# PWMsch.net
KiCad netlist of a schematic drawn in Altium Designer
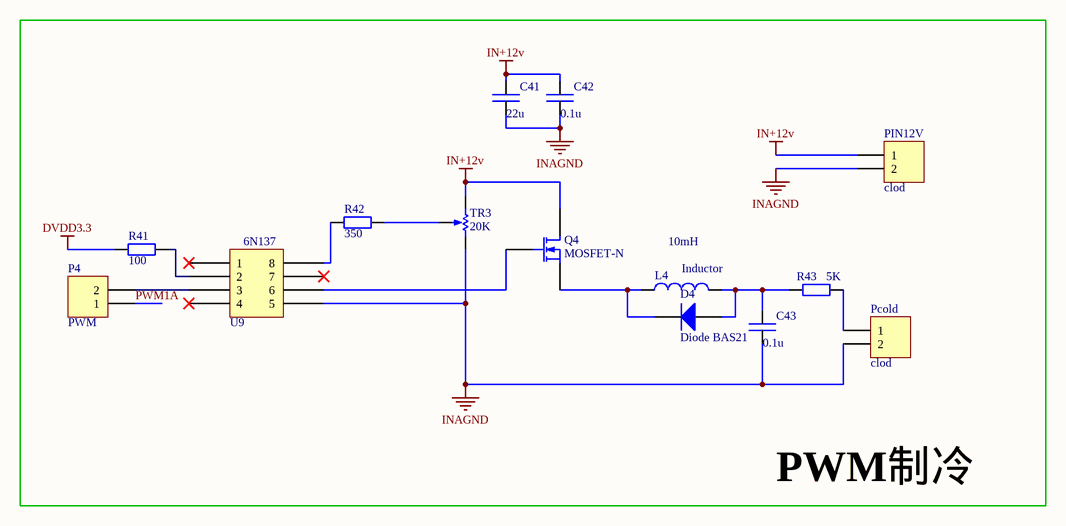
[diagram p0: PWMsch.SchDoc]

(export (version "E")
  (design (tool "Eeschema 10.0.6"))
  (components
    (comp (ref "C41") (value "22u") (footprint "4*4.5 贴片电解电容") (libsource (lib "LST") (part "Cap")))
    (comp (ref "C42") (value "0.1u") (footprint "0805") (libsource (lib "LST") (part "Cap")))
    (comp (ref "C43") (value "0.1u") (footprint "0805") (libsource (lib "LST") (part "Cap")))
    (comp (ref "D4")
      (value "Diode BAS21")
      (footprint "DIODE-SMA")
      (description "Silicon Switching Diode for High-Speed, High-Voltage Switching")
      (fields (field (name "PUBLISHER") "Altium Limited"))
      (libsource (lib "Miscellaneous Devices") (part "Diode BAS21"))
    )
    (comp (ref "L4")
      (value "Inductor")
      (footprint "1206")
      (fields (field (name "ALTIUM_VALUE") "10mH") (field (name "PUBLISHER") "Altium Limited"))
      (libsource (lib "Miscellaneous Devices") (part "Inductor"))
    )
    (comp (ref "P4")
      (value "PWM")
      (footprint "HDR1X2")
      (description "Header, 2-Pin")
      (fields (field (name "PUBLISHER") "Altium Limited"))
      (libsource (lib "") (part "Header 2_1"))
    )
    (comp (ref "Pcold")
      (value "clod")
      (footprint "HDR1X2")
      (description "Header, 2-Pin")
      (fields (field (name "PUBLISHER") "Altium Limited"))
      (libsource (lib "Miscellaneous Connectors") (part "Header 2"))
    )
    (comp (ref "PIN12V")
      (value "clod")
      (footprint "HDR1X2")
      (description "Header, 2-Pin")
      (fields (field (name "PUBLISHER") "Altium Limited"))
      (libsource (lib "Miscellaneous Connectors") (part "Header 2"))
    )
    (comp (ref "Q4")
      (value "MOSFET-N")
      (footprint "TIP122-带卧式散热")
      (description "N-Channel MOSFET")
      (fields (field (name "PUBLISHER") "Altium Limited"))
      (libsource (lib "Miscellaneous Devices") (part "MOSFET-N"))
    )
    (comp (ref "R41")
      (value "100")
      (footprint "0805")
      (description "Resistor")
      (fields (field (name "Comment") "Res2") (field (name "PUBLISHER") "Altium Limited"))
      (libsource (lib "Miscellaneous Devices") (part "Res2"))
    )
    (comp (ref "R42")
      (value "350")
      (footprint "0805")
      (description "Resistor")
      (fields (field (name "Comment") "Res2") (field (name "PUBLISHER") "Altium Limited"))
      (libsource (lib "Miscellaneous Devices") (part "Res2"))
    )
    (comp (ref "R43")
      (value "5K")
      (footprint "1206")
      (description "Resistor")
      (fields (field (name "Comment") "Res2") (field (name "PUBLISHER") "Altium Limited"))
      (libsource (lib "") (part "Res2_1"))
    )
    (comp (ref "TR3")
      (value "20K")
      (footprint "VR5")
      (description "Potentiometer")
      (fields (field (name "Comment") "RPot") (field (name "PUBLISHER") "Altium Limited"))
      (libsource (lib "Miscellaneous Devices") (part "RPot"))
    )
    (comp (ref "U9") (value "6N137") (footprint "SOIC8") (libsource (lib "cold") (part "6N137")))
  )
  (nets
    (net (code "1") (name "/PWM1A") (class "Default")
      (node (ref "P4") (pin "1") (pinfunction "1_1") (pintype "passive"))
    )
    (net (code "2") (name "DVDD3.3") (class "Default")
      (node (ref "R41") (pin "2") (pinfunction "2_2") (pintype "passive"))
    )
    (net (code "3") (name "IN+12v") (class "Default")
      (node (ref "C41") (pin "1") (pinfunction "1_1") (pintype "passive"))
      (node (ref "C42") (pin "1") (pinfunction "1_1") (pintype "passive"))
      (node (ref "PIN12V") (pin "1") (pinfunction "1_1") (pintype "passive"))
      (node (ref "Q4") (pin "2") (pinfunction "D_2") (pintype "passive"))
      (node (ref "TR3") (pin "1") (pinfunction "TOP_1") (pintype "passive"))
    )
    (net (code "4") (name "INAGND") (class "Default")
      (node (ref "C41") (pin "2") (pinfunction "2_2") (pintype "passive"))
      (node (ref "C42") (pin "2") (pinfunction "2_2") (pintype "passive"))
      (node (ref "C43") (pin "2") (pinfunction "2_2") (pintype "passive"))
      (node (ref "PIN12V") (pin "2") (pinfunction "2_2") (pintype "passive"))
      (node (ref "Pcold") (pin "2") (pinfunction "2_2") (pintype "passive"))
      (node (ref "TR3") (pin "3") (pinfunction "BOT_3") (pintype "passive"))
      (node (ref "U9") (pin "5") (pinfunction "5_5") (pintype "passive"))
    )
    (net (code "5") (name "Net-(D4-A)") (class "Default")
      (node (ref "C43") (pin "1") (pinfunction "1_1") (pintype "passive"))
      (node (ref "D4") (pin "1") (pinfunction "A_1") (pintype "passive"))
      (node (ref "L4") (pin "2") (pinfunction "2_2") (pintype "passive"))
      (node (ref "R43") (pin "1") (pinfunction "1_1") (pintype "passive"))
    )
    (net (code "6") (name "Net-(D4-K)") (class "Default")
      (node (ref "D4") (pin "3") (pinfunction "K_3") (pintype "passive"))
      (node (ref "L4") (pin "1") (pinfunction "1_1") (pintype "passive"))
      (node (ref "Q4") (pin "3") (pinfunction "S_3") (pintype "passive"))
    )
    (net (code "7") (name "Net-(P4-Pad2)") (class "Default")
      (node (ref "P4") (pin "2") (pinfunction "2_2") (pintype "passive"))
      (node (ref "U9") (pin "3") (pinfunction "3_3") (pintype "passive"))
    )
    (net (code "8") (name "Net-(Pcold-Pad1)") (class "Default")
      (node (ref "Pcold") (pin "1") (pinfunction "1_1") (pintype "passive"))
      (node (ref "R43") (pin "2") (pinfunction "2_2") (pintype "passive"))
    )
    (net (code "9") (name "Net-(Q4-G)") (class "Default")
      (node (ref "Q4") (pin "1") (pinfunction "G_1") (pintype "passive"))
      (node (ref "U9") (pin "6") (pinfunction "6_6") (pintype "passive"))
    )
    (net (code "10") (name "Net-(R41-Pad1)") (class "Default")
      (node (ref "R41") (pin "1") (pinfunction "1_1") (pintype "passive"))
      (node (ref "U9") (pin "2") (pinfunction "2_2") (pintype "passive"))
    )
    (net (code "11") (name "Net-(R42-Pad2)") (class "Default")
      (node (ref "R42") (pin "2") (pinfunction "2_2") (pintype "passive"))
      (node (ref "U9") (pin "8") (pinfunction "8_8") (pintype "passive"))
    )
    (net (code "12") (name "Net-(TR3-TAP)") (class "Default")
      (node (ref "R42") (pin "1") (pinfunction "1_1") (pintype "passive"))
      (node (ref "TR3") (pin "2") (pinfunction "TAP_2") (pintype "passive"))
    )
    (net (code "13") (name "unconnected-(U9-Pad1)") (class "Default")
      (node (ref "U9") (pin "1") (pinfunction "1_1") (pintype "passive+no_connect"))
    )
    (net (code "14") (name "unconnected-(U9-Pad4)") (class "Default")
      (node (ref "U9") (pin "4") (pinfunction "4_4") (pintype "passive+no_connect"))
    )
    (net (code "15") (name "unconnected-(U9-Pad7)") (class "Default")
      (node (ref "U9") (pin "7") (pinfunction "7_7") (pintype "passive+no_connect"))
    )
  )
)
